# main.net
KiCad netlist of a schematic drawn in EAGLE
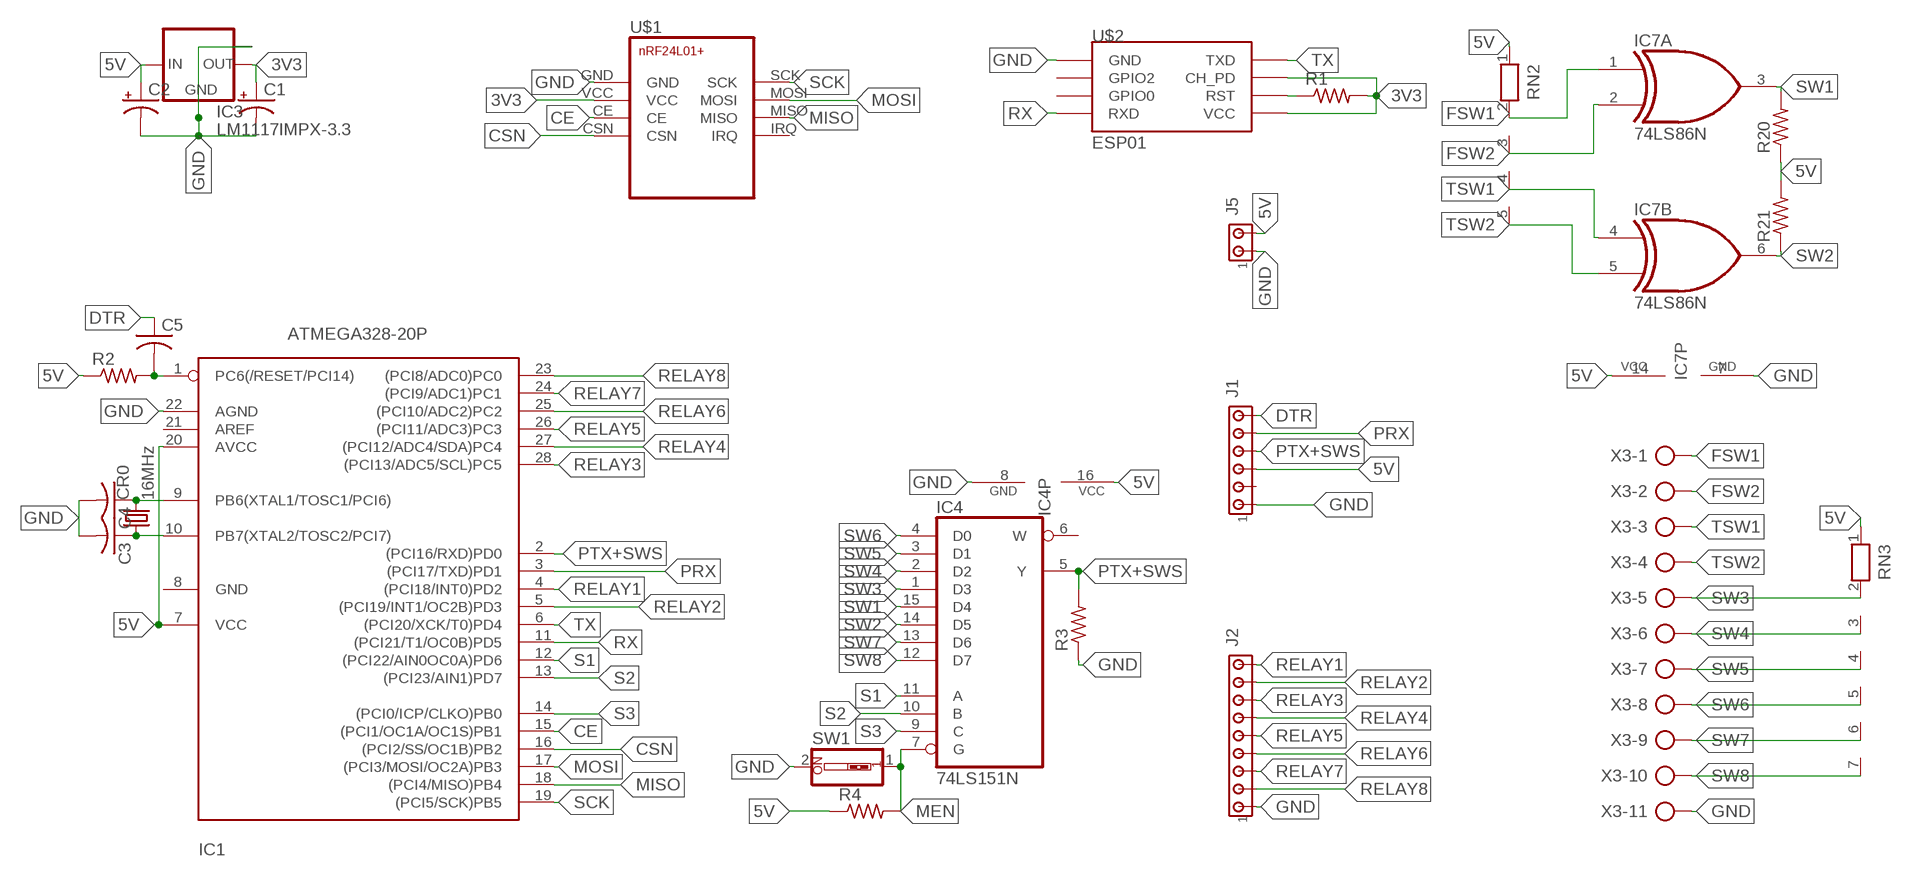
[diagram p0: schematic, sheet 1]

(export (version "E")
  (design (tool "Eeschema 10.0.6"))
  (components
    (comp (ref "C1")
      (value "CPOL-USE2,5-6E")
      (footprint "eagle-import:E2,5-6E")
      (libsource (lib "eagle-import") (part "CPOL-USE2,5-6E"))
    )
    (comp (ref "C2")
      (value "CPOL-USE2,5-6E")
      (footprint "eagle-import:E2,5-6E")
      (libsource (lib "eagle-import") (part "CPOL-USE2,5-6E"))
    )
    (comp (ref "C3")
      (value "C-USC1206")
      (footprint "eagle-import:C1206")
      (libsource (lib "eagle-import") (part "C-USC1206"))
    )
    (comp (ref "C4")
      (value "C-USC1206")
      (footprint "eagle-import:C1206")
      (libsource (lib "eagle-import") (part "C-USC1206"))
    )
    (comp (ref "C5")
      (value "C-USC1206")
      (footprint "eagle-import:C1206")
      (libsource (lib "eagle-import") (part "C-USC1206"))
    )
    (comp (ref "CR0")
      (value "16MHz")
      (footprint "eagle-import:HC18U-V")
      (libsource (lib "eagle-import") (part "CRYSTALHC18U-V"))
    )
    (comp (ref "IC1")
      (value "ATMEGA328-20P")
      (footprint "eagle-import:DIL28-3")
      (libsource (lib "eagle-import") (part "ATMEGA328P-20"))
    )
    (comp (ref "IC3")
      (value "LM1117IMPX-3.3")
      (footprint "eagle-import:SOT223")
      (libsource (lib "eagle-import") (part "LM1117IMPX-3.3"))
    )
    (comp (ref "IC4")
      (value "74LS151N")
      (footprint "eagle-import:DIL16")
      (libsource (lib "eagle-import") (part "74151NLS"))
    )
    (comp (ref "IC7")
      (value "74LS86N")
      (footprint "eagle-import:DIL14")
      (libsource (lib "eagle-import") (part "7486NLS"))
    )
    (comp (ref "J1")
      (value "MTA06-100")
      (footprint "eagle-import:10X06MTA")
      (libsource (lib "eagle-import") (part "MTA06-100"))
    )
    (comp (ref "J2")
      (value "MTA09-100")
      (footprint "eagle-import:10X09MTA")
      (libsource (lib "eagle-import") (part "MTA09-100"))
    )
    (comp (ref "J5")
      (value "MTA02-100")
      (footprint "eagle-import:10X02MTA")
      (libsource (lib "eagle-import") (part "MTA02-100"))
    )
    (comp (ref "R1")
      (value "R-US_R1206")
      (footprint "eagle-import:R1206")
      (libsource (lib "eagle-import") (part "R-US_R1206"))
    )
    (comp (ref "R2")
      (value "R-US_R1206")
      (footprint "eagle-import:R1206")
      (libsource (lib "eagle-import") (part "R-US_R1206"))
    )
    (comp (ref "R3")
      (value "R-US_R1206")
      (footprint "eagle-import:R1206")
      (libsource (lib "eagle-import") (part "R-US_R1206"))
    )
    (comp (ref "R4")
      (value "R-US_R1206")
      (footprint "eagle-import:R1206")
      (libsource (lib "eagle-import") (part "R-US_R1206"))
    )
    (comp (ref "R20")
      (value "R-US_0204/7")
      (footprint "eagle-import:0204_7")
      (libsource (lib "eagle-import") (part "R-US_0204/7"))
    )
    (comp (ref "R21")
      (value "R-US_R1206")
      (footprint "eagle-import:R1206")
      (libsource (lib "eagle-import") (part "R-US_R1206"))
    )
    (comp (ref "RN2")
      (value "RN04")
      (footprint "eagle-import:RN-5")
      (libsource (lib "eagle-import") (part "RN04"))
    )
    (comp (ref "RN3")
      (value "RN06")
      (footprint "eagle-import:RN-7")
      (libsource (lib "eagle-import") (part "RN06"))
    )
    (comp (ref "SW1")
      (value "SW_DIP-1")
      (footprint "eagle-import:EDG-01")
      (libsource (lib "eagle-import") (part "SW_DIP-1"))
    )
    (comp (ref "U$1")
      (value "NRF24L01+")
      (footprint "eagle-import:NRF24L01+")
      (libsource (lib "eagle-import") (part "NRF24L01+"))
    )
    (comp (ref "U$2")
      (value "ESP01")
      (footprint "eagle-import:ESP01")
      (libsource (lib "eagle-import") (part "ESP01"))
    )
    (comp (ref "X3")
      (value "AK300/11")
      (footprint "eagle-import:AK300_11")
      (libsource (lib "eagle-import") (part "AK300/11"))
    )
  )
  (nets
    (net (code "1") (name "3V3") (class "Default")
      (node (ref "C1") (pin "+") (pinfunction "+_+") (pintype "passive"))
      (node (ref "IC3") (pin "2") (pinfunction "OUT_2") (pintype "passive"))
      (node (ref "R1") (pin "2") (pinfunction "2_2") (pintype "passive"))
      (node (ref "U$1") (pin "VCC") (pinfunction "VCC_VCC") (pintype "power_in"))
      (node (ref "U$2") (pin "CH_PD") (pinfunction "CH_PD_CH_PD") (pintype "bidirectional"))
      (node (ref "U$2") (pin "VCC") (pinfunction "VCC_VCC") (pintype "bidirectional"))
    )
    (net (code "2") (name "5V") (class "Default")
      (node (ref "C2") (pin "+") (pinfunction "+_+") (pintype "passive"))
      (node (ref "IC1") (pin "20") (pinfunction "AVCC_20") (pintype "bidirectional"))
      (node (ref "IC1") (pin "7") (pinfunction "VCC_7") (pintype "bidirectional"))
      (node (ref "IC3") (pin "3") (pinfunction "IN_3") (pintype "input"))
      (node (ref "IC4") (pin "16") (pinfunction "VCC_16") (pintype "power_in"))
      (node (ref "IC7") (pin "14") (pinfunction "VCC_14") (pintype "power_in"))
      (node (ref "J1") (pin "3") (pinfunction "3_3") (pintype "passive"))
      (node (ref "J5") (pin "2") (pinfunction "2_2") (pintype "passive"))
      (node (ref "R2") (pin "1") (pinfunction "1_1") (pintype "passive"))
      (node (ref "R20") (pin "1") (pinfunction "1_1") (pintype "passive"))
      (node (ref "R21") (pin "2") (pinfunction "2_2") (pintype "passive"))
      (node (ref "R4") (pin "1") (pinfunction "1_1") (pintype "passive"))
      (node (ref "RN2") (pin "1") (pinfunction "1_1") (pintype "passive"))
      (node (ref "RN3") (pin "1") (pinfunction "1_1") (pintype "passive"))
    )
    (net (code "3") (name "CE") (class "Default")
      (node (ref "IC1") (pin "15") (pinfunction "(PCI1/OC1A/OC1S)PB1_15") (pintype "bidirectional"))
      (node (ref "U$1") (pin "CE") (pinfunction "CE_CE") (pintype "bidirectional"))
    )
    (net (code "4") (name "CSN") (class "Default")
      (node (ref "IC1") (pin "16") (pinfunction "(PCI2/SS/OC1B)PB2_16") (pintype "bidirectional"))
      (node (ref "U$1") (pin "CSN") (pinfunction "CSN_CSN") (pintype "bidirectional"))
    )
    (net (code "5") (name "DTR") (class "Default")
      (node (ref "C5") (pin "1") (pinfunction "1_1") (pintype "passive"))
      (node (ref "J1") (pin "6") (pinfunction "6_6") (pintype "passive"))
    )
    (net (code "6") (name "FSW1") (class "Default")
      (node (ref "IC7") (pin "1") (pinfunction "I0_1") (pintype "input"))
      (node (ref "RN2") (pin "2") (pinfunction "2_2") (pintype "passive"))
      (node (ref "X3") (pin "1") (pinfunction "KL_1") (pintype "passive"))
    )
    (net (code "7") (name "FSW2") (class "Default")
      (node (ref "IC7") (pin "2") (pinfunction "I1_2") (pintype "input"))
      (node (ref "RN2") (pin "3") (pinfunction "3_3") (pintype "passive"))
      (node (ref "X3") (pin "2") (pinfunction "KL_2") (pintype "passive"))
    )
    (net (code "8") (name "GND") (class "Default")
      (node (ref "C1") (pin "-") (pinfunction "-_-") (pintype "passive"))
      (node (ref "C2") (pin "-") (pinfunction "-_-") (pintype "passive"))
      (node (ref "C3") (pin "2") (pinfunction "2_2") (pintype "passive"))
      (node (ref "C4") (pin "2") (pinfunction "2_2") (pintype "passive"))
      (node (ref "IC1") (pin "22") (pinfunction "AGND_22") (pintype "bidirectional"))
      (node (ref "IC3") (pin "1") (pinfunction "GND_1") (pintype "input"))
      (node (ref "IC3") (pin "TAB") (pinfunction "OUT1_TAB") (pintype "passive"))
      (node (ref "IC4") (pin "8") (pinfunction "GND_8") (pintype "power_in"))
      (node (ref "IC7") (pin "7") (pinfunction "GND_7") (pintype "power_in"))
      (node (ref "J1") (pin "1") (pinfunction "1_1") (pintype "passive"))
      (node (ref "J2") (pin "1") (pinfunction "1_1") (pintype "passive"))
      (node (ref "J5") (pin "1") (pinfunction "1_1") (pintype "passive"))
      (node (ref "R3") (pin "1") (pinfunction "1_1") (pintype "passive"))
      (node (ref "SW1") (pin "2") (pinfunction "2_2") (pintype "passive"))
      (node (ref "U$1") (pin "GND") (pinfunction "GND_GND") (pintype "power_in"))
      (node (ref "U$2") (pin "GND") (pinfunction "GND_GND") (pintype "bidirectional"))
      (node (ref "X3") (pin "11") (pinfunction "KL_11") (pintype "passive"))
    )
    (net (code "9") (name "MEN") (class "Default")
      (node (ref "IC4") (pin "7") (pinfunction "G_7") (pintype "input"))
      (node (ref "R4") (pin "2") (pinfunction "2_2") (pintype "passive"))
      (node (ref "SW1") (pin "1") (pinfunction "1_1") (pintype "passive"))
    )
    (net (code "10") (name "MISO") (class "Default")
      (node (ref "IC1") (pin "18") (pinfunction "(PCI4/MISO)PB4_18") (pintype "bidirectional"))
      (node (ref "U$1") (pin "MISO") (pinfunction "MISO_MISO") (pintype "bidirectional"))
    )
    (net (code "11") (name "MOSI") (class "Default")
      (node (ref "IC1") (pin "17") (pinfunction "(PCI3/MOSI/OC2A)PB3_17") (pintype "bidirectional"))
      (node (ref "U$1") (pin "MOSI") (pinfunction "MOSI_MOSI") (pintype "bidirectional"))
    )
    (net (code "12") (name "Net-(IC1-PB6(XTAL1{slash}TOSC1{slash}PCI6))") (class "Default")
      (node (ref "C4") (pin "1") (pinfunction "1_1") (pintype "passive"))
      (node (ref "CR0") (pin "2") (pinfunction "2_2") (pintype "passive"))
      (node (ref "IC1") (pin "9") (pinfunction "PB6(XTAL1/TOSC1/PCI6)_9") (pintype "bidirectional"))
    )
    (net (code "13") (name "Net-(IC1-PB7(XTAL2{slash}TOSC2{slash}PCI7))") (class "Default")
      (node (ref "C3") (pin "1") (pinfunction "1_1") (pintype "passive"))
      (node (ref "CR0") (pin "1") (pinfunction "1_1") (pintype "passive"))
      (node (ref "IC1") (pin "10") (pinfunction "PB7(XTAL2/TOSC2/PCI7)_10") (pintype "bidirectional"))
    )
    (net (code "14") (name "Net-(IC1-PC6({slash}RESET{slash}PCI14))") (class "Default")
      (node (ref "C5") (pin "2") (pinfunction "2_2") (pintype "passive"))
      (node (ref "IC1") (pin "1") (pinfunction "PC6(/RESET/PCI14)_1") (pintype "bidirectional"))
      (node (ref "R2") (pin "2") (pinfunction "2_2") (pintype "passive"))
    )
    (net (code "15") (name "Net-(R1-Pad1)") (class "Default")
      (node (ref "R1") (pin "1") (pinfunction "1_1") (pintype "passive"))
      (node (ref "U$2") (pin "RST") (pinfunction "RST_RST") (pintype "bidirectional"))
    )
    (net (code "16") (name "PRX") (class "Default")
      (node (ref "IC1") (pin "3") (pinfunction "(PCI17/TXD)PD1_3") (pintype "bidirectional"))
      (node (ref "J1") (pin "5") (pinfunction "5_5") (pintype "passive"))
    )
    (net (code "17") (name "PTX+SWS") (class "Default")
      (node (ref "IC1") (pin "2") (pinfunction "(PCI16/RXD)PD0_2") (pintype "bidirectional"))
      (node (ref "IC4") (pin "5") (pinfunction "Y_5") (pintype "output"))
      (node (ref "J1") (pin "4") (pinfunction "4_4") (pintype "passive"))
      (node (ref "R3") (pin "2") (pinfunction "2_2") (pintype "passive"))
    )
    (net (code "18") (name "RELAY1") (class "Default")
      (node (ref "IC1") (pin "4") (pinfunction "(PCI18/INT0)PD2_4") (pintype "bidirectional"))
      (node (ref "J2") (pin "9") (pinfunction "9_9") (pintype "passive"))
    )
    (net (code "19") (name "RELAY2") (class "Default")
      (node (ref "IC1") (pin "5") (pinfunction "(PCI19/INT1/OC2B)PD3_5") (pintype "bidirectional"))
      (node (ref "J2") (pin "8") (pinfunction "8_8") (pintype "passive"))
    )
    (net (code "20") (name "RELAY3") (class "Default")
      (node (ref "IC1") (pin "28") (pinfunction "(PCI13/ADC5/SCL)PC5_28") (pintype "bidirectional"))
      (node (ref "J2") (pin "7") (pinfunction "7_7") (pintype "passive"))
    )
    (net (code "21") (name "RELAY4") (class "Default")
      (node (ref "IC1") (pin "27") (pinfunction "(PCI12/ADC4/SDA)PC4_27") (pintype "bidirectional"))
      (node (ref "J2") (pin "6") (pinfunction "6_6") (pintype "passive"))
    )
    (net (code "22") (name "RELAY5") (class "Default")
      (node (ref "IC1") (pin "26") (pinfunction "(PCI11/ADC3)PC3_26") (pintype "bidirectional"))
      (node (ref "J2") (pin "5") (pinfunction "5_5") (pintype "passive"))
    )
    (net (code "23") (name "RELAY6") (class "Default")
      (node (ref "IC1") (pin "25") (pinfunction "(PCI10/ADC2)PC2_25") (pintype "bidirectional"))
      (node (ref "J2") (pin "4") (pinfunction "4_4") (pintype "passive"))
    )
    (net (code "24") (name "RELAY7") (class "Default")
      (node (ref "IC1") (pin "24") (pinfunction "(PCI9/ADC1)PC1_24") (pintype "bidirectional"))
      (node (ref "J2") (pin "3") (pinfunction "3_3") (pintype "passive"))
    )
    (net (code "25") (name "RELAY8") (class "Default")
      (node (ref "IC1") (pin "23") (pinfunction "(PCI8/ADC0)PC0_23") (pintype "bidirectional"))
      (node (ref "J2") (pin "2") (pinfunction "2_2") (pintype "passive"))
    )
    (net (code "26") (name "RX") (class "Default")
      (node (ref "IC1") (pin "11") (pinfunction "(PCI21/T1/OC0B)PD5_11") (pintype "bidirectional"))
      (node (ref "U$2") (pin "RX") (pinfunction "RXD_RX") (pintype "bidirectional"))
    )
    (net (code "27") (name "S1") (class "Default")
      (node (ref "IC1") (pin "12") (pinfunction "(PCI22/AIN0OC0A)PD6_12") (pintype "bidirectional"))
      (node (ref "IC4") (pin "11") (pinfunction "A_11") (pintype "input"))
    )
    (net (code "28") (name "S2") (class "Default")
      (node (ref "IC1") (pin "13") (pinfunction "(PCI23/AIN1)PD7_13") (pintype "bidirectional"))
      (node (ref "IC4") (pin "10") (pinfunction "B_10") (pintype "input"))
    )
    (net (code "29") (name "S3") (class "Default")
      (node (ref "IC1") (pin "14") (pinfunction "(PCI0/ICP/CLKO)PB0_14") (pintype "bidirectional"))
      (node (ref "IC4") (pin "9") (pinfunction "C_9") (pintype "input"))
    )
    (net (code "30") (name "SCK") (class "Default")
      (node (ref "IC1") (pin "19") (pinfunction "(PCI5/SCK)PB5_19") (pintype "bidirectional"))
      (node (ref "U$1") (pin "SCK") (pinfunction "SCK_SCK") (pintype "bidirectional"))
    )
    (net (code "31") (name "SW1") (class "Default")
      (node (ref "IC4") (pin "15") (pinfunction "D4_15") (pintype "input"))
      (node (ref "IC7") (pin "3") (pinfunction "O_3") (pintype "output"))
      (node (ref "R20") (pin "2") (pinfunction "2_2") (pintype "passive"))
    )
    (net (code "32") (name "SW2") (class "Default")
      (node (ref "IC4") (pin "14") (pinfunction "D5_14") (pintype "input"))
      (node (ref "IC7") (pin "6") (pinfunction "O_6") (pintype "output"))
      (node (ref "R21") (pin "1") (pinfunction "1_1") (pintype "passive"))
    )
    (net (code "33") (name "SW3") (class "Default")
      (node (ref "IC4") (pin "1") (pinfunction "D3_1") (pintype "input"))
      (node (ref "RN3") (pin "2") (pinfunction "2_2") (pintype "passive"))
      (node (ref "X3") (pin "5") (pinfunction "KL_5") (pintype "passive"))
    )
    (net (code "34") (name "SW4") (class "Default")
      (node (ref "IC4") (pin "2") (pinfunction "D2_2") (pintype "input"))
      (node (ref "RN3") (pin "3") (pinfunction "3_3") (pintype "passive"))
      (node (ref "X3") (pin "6") (pinfunction "KL_6") (pintype "passive"))
    )
    (net (code "35") (name "SW5") (class "Default")
      (node (ref "IC4") (pin "3") (pinfunction "D1_3") (pintype "input"))
      (node (ref "RN3") (pin "4") (pinfunction "4_4") (pintype "passive"))
      (node (ref "X3") (pin "7") (pinfunction "KL_7") (pintype "passive"))
    )
    (net (code "36") (name "SW6") (class "Default")
      (node (ref "IC4") (pin "4") (pinfunction "D0_4") (pintype "input"))
      (node (ref "RN3") (pin "5") (pinfunction "5_5") (pintype "passive"))
      (node (ref "X3") (pin "8") (pinfunction "KL_8") (pintype "passive"))
    )
    (net (code "37") (name "SW7") (class "Default")
      (node (ref "IC4") (pin "13") (pinfunction "D6_13") (pintype "input"))
      (node (ref "RN3") (pin "6") (pinfunction "6_6") (pintype "passive"))
      (node (ref "X3") (pin "9") (pinfunction "KL_9") (pintype "passive"))
    )
    (net (code "38") (name "SW8") (class "Default")
      (node (ref "IC4") (pin "12") (pinfunction "D7_12") (pintype "input"))
      (node (ref "RN3") (pin "7") (pinfunction "7_7") (pintype "passive"))
      (node (ref "X3") (pin "10") (pinfunction "KL_10") (pintype "passive"))
    )
    (net (code "39") (name "TSW1") (class "Default")
      (node (ref "IC7") (pin "4") (pinfunction "I0_4") (pintype "input"))
      (node (ref "RN2") (pin "4") (pinfunction "4_4") (pintype "passive"))
      (node (ref "X3") (pin "3") (pinfunction "KL_3") (pintype "passive"))
    )
    (net (code "40") (name "TSW2") (class "Default")
      (node (ref "IC7") (pin "5") (pinfunction "I1_5") (pintype "input"))
      (node (ref "RN2") (pin "5") (pinfunction "5_5") (pintype "passive"))
      (node (ref "X3") (pin "4") (pinfunction "KL_4") (pintype "passive"))
    )
    (net (code "41") (name "TX") (class "Default")
      (node (ref "IC1") (pin "6") (pinfunction "(PCI20/XCK/T0)PD4_6") (pintype "bidirectional"))
      (node (ref "U$2") (pin "TX") (pinfunction "TXD_TX") (pintype "bidirectional"))
    )
    (net (code "42") (name "unconnected-(IC1-AREF-Pad21)") (class "Default")
      (node (ref "IC1") (pin "21") (pinfunction "AREF_21") (pintype "bidirectional"))
    )
    (net (code "43") (name "unconnected-(IC1-GND-Pad8)") (class "Default")
      (node (ref "IC1") (pin "8") (pinfunction "GND_8") (pintype "bidirectional"))
    )
    (net (code "44") (name "unconnected-(IC4A-W-Pad6)") (class "Default")
      (node (ref "IC4") (pin "6") (pinfunction "W_6") (pintype "output"))
    )
    (net (code "45") (name "unconnected-(J1-Pad2)") (class "Default")
      (node (ref "J1") (pin "2") (pinfunction "2_2") (pintype "passive"))
    )
    (net (code "46") (name "unconnected-(U$1-PadIRQ)") (class "Default")
      (node (ref "U$1") (pin "IRQ") (pinfunction "IRQ_IRQ") (pintype "bidirectional"))
    )
    (net (code "47") (name "unconnected-(U$2-PadGPIO0)") (class "Default")
      (node (ref "U$2") (pin "GPIO0") (pinfunction "GPIO0_GPIO0") (pintype "bidirectional"))
    )
    (net (code "48") (name "unconnected-(U$2-PadGPIO2)") (class "Default")
      (node (ref "U$2") (pin "GPIO2") (pinfunction "GPIO2_GPIO2") (pintype "bidirectional"))
    )
  )
)
